# ECU_Power.net
KiCad netlist of a schematic drawn in Altium Designer
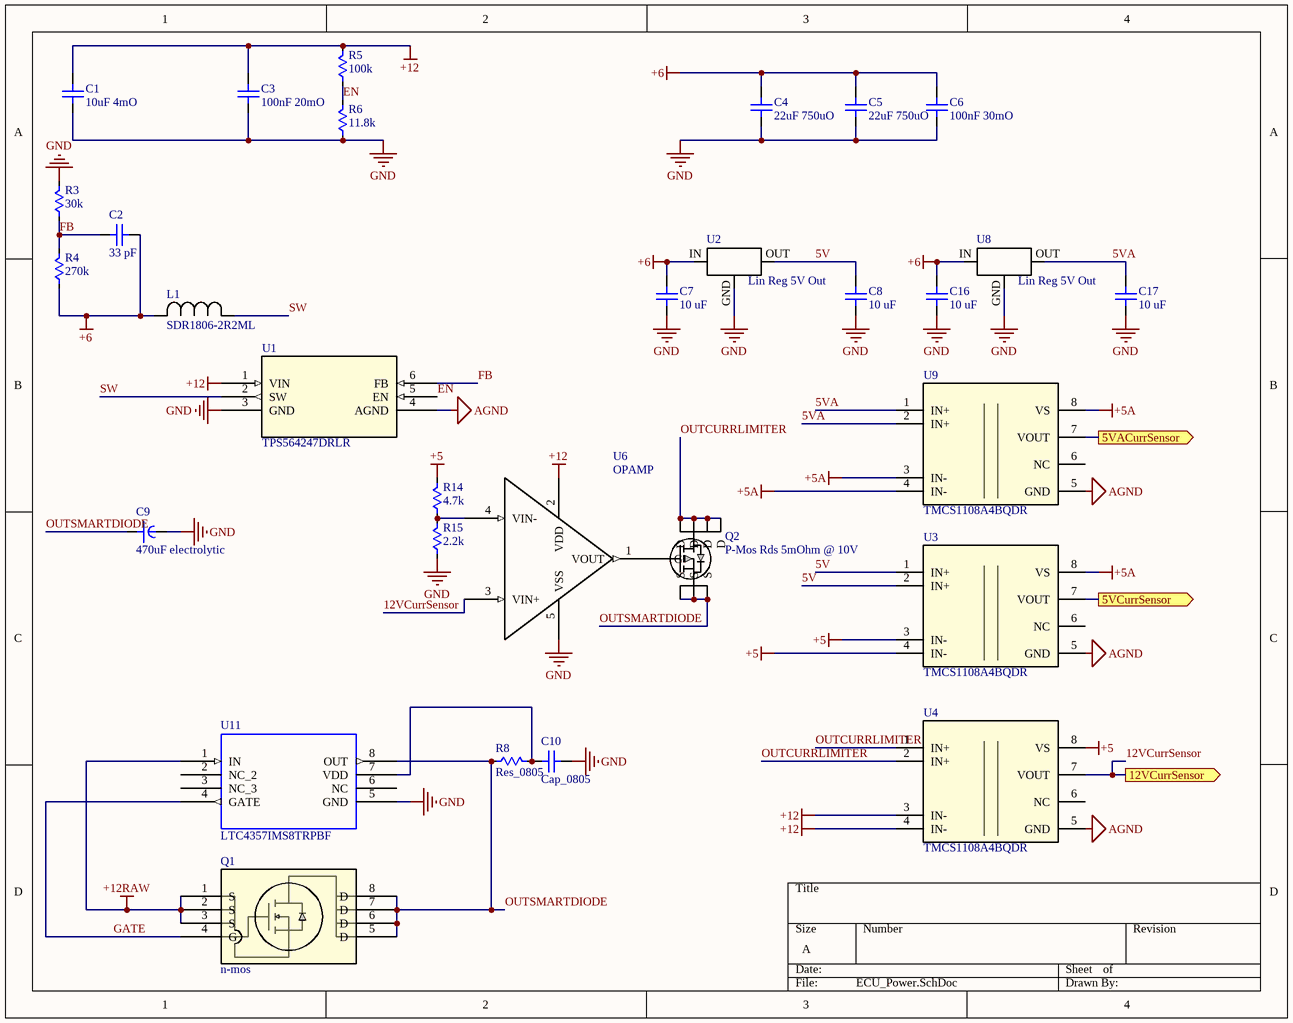
[diagram p0: ECU_Power.SchDoc]

(export (version "E")
  (design (tool "Eeschema 10.0.6"))
  (components
    (comp (ref "C1")
      (value "10uF 4mO")
      (footprint "0805")
      (description "Cap 0805")
      (libsource (lib "Caps") (part "Cap_0805"))
    )
    (comp (ref "C2")
      (value "33 pF")
      (footprint "0805")
      (description "Cap 0805 - 33 pF, 1mOhm")
      (libsource (lib "Caps") (part "Cap_0805"))
    )
    (comp (ref "C3")
      (value "100nF 20mO")
      (footprint "0805")
      (description "Cap 0805")
      (libsource (lib "Caps") (part "Cap_0805"))
    )
    (comp (ref "C4")
      (value "22uF 750uO")
      (footprint "0805")
      (description "Cap 0805")
      (libsource (lib "Caps") (part "Cap_0805"))
    )
    (comp (ref "C5")
      (value "22uF 750uO")
      (footprint "0805")
      (description "Cap 0805")
      (libsource (lib "Caps") (part "Cap_0805"))
    )
    (comp (ref "C6")
      (value "100nF 30mO")
      (footprint "0805")
      (description "Cap 0805")
      (libsource (lib "Caps") (part "Cap_0805"))
    )
    (comp (ref "C7")
      (value "10 uF")
      (footprint "0805")
      (description "Cap 0805")
      (libsource (lib "Caps") (part "Cap_0805"))
    )
    (comp (ref "C8")
      (value "10 uF")
      (footprint "0805")
      (description "Cap 0805")
      (libsource (lib "Caps") (part "Cap_0805"))
    )
    (comp (ref "C9")
      (value "470uF electrolytic")
      (footprint "CAPPRD750W80D1600H2700")
      (description "470 µF 100 V Aluminum Electrolytic Capacitors Radial, Can 282mOhm @ 120Hz 2000 Hrs @ 85°C")
      (libsource (lib "Caps") (part "CAPPRD750W80D1600H2700"))
    )
    (comp (ref "C10")
      (value "Cap_0805")
      (footprint "0805")
      (description "Cap 0805")
      (libsource (lib "Caps") (part "Cap_0805"))
    )
    (comp (ref "C16")
      (value "10 uF")
      (footprint "0805")
      (description "Cap 0805")
      (libsource (lib "Caps") (part "Cap_0805"))
    )
    (comp (ref "C17")
      (value "10 uF")
      (footprint "0805")
      (description "Cap 0805")
      (libsource (lib "Caps") (part "Cap_0805"))
    )
    (comp (ref "L1")
      (value "SDR1806-2R2ML")
      (footprint "IND_BOURNS_SDR1806")
      (description "No Description Available")
      (fields (field (name "COPYRIGHT") "Copyright (C) 2022 Ultra Librarian. All rights reserved."))
      (libsource (lib "SDR1806-2R2ML") (part "SDR1806-2R2ML"))
    )
    (comp (ref "Q1")
      (value "n-mos")
      (footprint "D0008A-IPC_A")
      (description "MOSFET MOSFETBVDSS: 25V-30V")
      (libsource (lib "DMN3007LSSQ-13") (part "DMN3007LSSQ-13"))
    )
    (comp (ref "Q2")
      (value "P-Mos Rds 5mOhm @ 10V")
      (footprint "D0008A-IPC_A")
      (description "P-Channel 30 V 16A (Ta) 2.5W (Ta) Surface Mount 8-SOP")
      (fields
        (field (name "MANUFACTURER_PART_NUMBER") "UPA2735GR-E1-AT")
        (field (name "COPYRIGHT") "Copyright (C) 2022 Ultra Librarian. All rights reserved.")
      )
      (libsource (lib "UPA2735GR-E1-AT") (part "UPA2735GR-E1-AT"))
    )
    (comp (ref "R3")
      (value "30k")
      (footprint "0805")
      (description "Res 0805 - 30kOhm")
      (libsource (lib "Resistors") (part "Res_0805"))
    )
    (comp (ref "R4")
      (value "270k")
      (footprint "0805")
      (description "Res 0805 - 270kOhm")
      (libsource (lib "Resistors") (part "Res_0805"))
    )
    (comp (ref "R5")
      (value "100k")
      (footprint "0805")
      (description "Res 0805")
      (libsource (lib "Resistors") (part "Res_0805"))
    )
    (comp (ref "R6")
      (value "11.8k")
      (footprint "0805")
      (description "Res 0805")
      (libsource (lib "Resistors") (part "Res_0805"))
    )
    (comp (ref "R8")
      (value "Res_0805")
      (footprint "0805")
      (description "Res 0805")
      (libsource (lib "Resistors") (part "Res_0805"))
    )
    (comp (ref "R14")
      (value "4.7k")
      (footprint "0805")
      (description "Res 0805")
      (libsource (lib "Resistors") (part "Res_0805"))
    )
    (comp (ref "R15")
      (value "2.2k")
      (footprint "0805")
      (description "Res 0805")
      (libsource (lib "Resistors") (part "Res_0805"))
    )
    (comp (ref "U1")
      (value "TPS564247DRLR")
      (footprint "SOT5x3-6_DRL_TEX")
      (description "No Description Available")
      (fields (field (name "COPYRIGHT") "Copyright (C) 2022 Ultra Librarian. All rights reserved."))
      (libsource (lib "TPS564247DRLR") (part "TPS564247DRLR"))
    )
    (comp (ref "U2")
      (value "Lin Reg 5V Out")
      (footprint "NCP1117IDT50T4G")
      (description "Linear Voltage Regulator IC Positive Fixed 1 Output 1A DPAK")
      (libsource (lib "NCP1117IDT50T4G") (part "NCP1117IDT50T4G"))
    )
    (comp (ref "U3")
      (value "TMCS1108A4BQDR")
      (footprint "D0008A-IPC_A")
      (description "No Description Available")
      (fields (field (name "COPYRIGHT") "Copyright (C) 2022 Ultra Librarian. All rights reserved."))
      (libsource (lib "TMCS1108A4BQDR") (part "TMCS1108A4BQDR"))
    )
    (comp (ref "U4")
      (value "TMCS1108A4BQDR")
      (footprint "D0008A-IPC_A")
      (description "No Description Available")
      (fields (field (name "COPYRIGHT") "Copyright (C) 2022 Ultra Librarian. All rights reserved."))
      (libsource (lib "TMCS1108A4BQDR") (part "TMCS1108A4BQDR"))
    )
    (comp (ref "U6")
      (value "OPAMP")
      (footprint "SOT-23-5_MC_MCH-M")
      (description "Operational Amplifiers - Op Amps Single, 10MHz Op Amp, E Temp")
      (fields
        (field (name "MANUFACTURER_PART_NUMBER") "MCP6486T-EOT")
        (field (name "COPYRIGHT") "Copyright (C) 2022 Ultra Librarian. All rights reserved.")
      )
      (libsource (lib "MCP6486T-EOT") (part "MCP6486T-EOT"))
    )
    (comp (ref "U8")
      (value "Lin Reg 5V Out")
      (footprint "NCP1117IDT50T4G")
      (description "Linear Voltage Regulator IC Positive Fixed 1 Output 1A DPAK")
      (libsource (lib "NCP1117IDT50T4G") (part "NCP1117IDT50T4G"))
    )
    (comp (ref "U9")
      (value "TMCS1108A4BQDR")
      (footprint "D0008A-IPC_A")
      (description "No Description Available")
      (fields (field (name "COPYRIGHT") "Copyright (C) 2022 Ultra Librarian. All rights reserved."))
      (libsource (lib "TMCS1108A4BQDR") (part "TMCS1108A4BQDR"))
    )
    (comp (ref "U11")
      (value "LTC4357IMS8TRPBF")
      (footprint "MSOP-8_MS:MSOP-8_MS")
      (description "OR Controller N+1 ORing Controller N-Channel N:1 8-MSOP")
      (fields (field (name "MF") "Analog Devices") (field (name "MP") "LTC4357IMS8#TRPBF"))
      (libsource (lib "LTC4357IMS8TRPBF") (part "LTC4357IMS8TRPBF"))
    )
  )
  (nets
    (net (code "1") (name "+5") (class "Default")
      (node (ref "R14") (pin "2") (pinfunction "2_2") (pintype "passive"))
      (node (ref "U3") (pin "3") (pinfunction "IN-_3") (pintype "passive"))
      (node (ref "U3") (pin "4") (pinfunction "IN-_4") (pintype "passive"))
      (node (ref "U4") (pin "8") (pinfunction "VS_8") (pintype "power_in"))
    )
    (net (code "2") (name "+5A") (class "Default")
      (node (ref "U3") (pin "8") (pinfunction "VS_8") (pintype "power_in"))
      (node (ref "U9") (pin "3") (pinfunction "IN-_3") (pintype "passive"))
      (node (ref "U9") (pin "4") (pinfunction "IN-_4") (pintype "passive"))
      (node (ref "U9") (pin "8") (pinfunction "VS_8") (pintype "power_in"))
    )
    (net (code "3") (name "+6") (class "Default")
      (node (ref "C16") (pin "2") (pinfunction "2_2") (pintype "passive"))
      (node (ref "C2") (pin "2") (pinfunction "2_2") (pintype "passive"))
      (node (ref "C4") (pin "2") (pinfunction "2_2") (pintype "passive"))
      (node (ref "C5") (pin "2") (pinfunction "2_2") (pintype "passive"))
      (node (ref "C6") (pin "2") (pinfunction "2_2") (pintype "passive"))
      (node (ref "C7") (pin "2") (pinfunction "2_2") (pintype "passive"))
      (node (ref "L1") (pin "2") (pinfunction "2_2") (pintype "passive"))
      (node (ref "R4") (pin "1") (pinfunction "1_1") (pintype "passive"))
      (node (ref "U2") (pin "IN") (pinfunction "IN_IN") (pintype "passive"))
      (node (ref "U8") (pin "IN") (pinfunction "IN_IN") (pintype "passive"))
    )
    (net (code "4") (name "+12") (class "Default")
      (node (ref "C1") (pin "2") (pinfunction "2_2") (pintype "passive"))
      (node (ref "C3") (pin "2") (pinfunction "2_2") (pintype "passive"))
      (node (ref "R5") (pin "2") (pinfunction "2_2") (pintype "passive"))
      (node (ref "U1") (pin "1") (pinfunction "VIN_1") (pintype "input"))
      (node (ref "U4") (pin "3") (pinfunction "IN-_3") (pintype "passive"))
      (node (ref "U4") (pin "4") (pinfunction "IN-_4") (pintype "passive"))
      (node (ref "U6") (pin "2") (pinfunction "VDD_2") (pintype "power_in"))
    )
    (net (code "5") (name "+12RAW") (class "Default")
      (node (ref "Q1") (pin "1") (pinfunction "S_1") (pintype "passive"))
      (node (ref "Q1") (pin "2") (pinfunction "S_2") (pintype "passive"))
      (node (ref "Q1") (pin "3") (pinfunction "S_3") (pintype "passive"))
      (node (ref "U11") (pin "1") (pinfunction "IN_1") (pintype "input"))
    )
    (net (code "6") (name "/5V") (class "Default")
      (node (ref "C8") (pin "2") (pinfunction "2_2") (pintype "passive"))
      (node (ref "U2") (pin "OUT") (pinfunction "OUT_OUT") (pintype "passive"))
      (node (ref "U3") (pin "1") (pinfunction "IN+_1") (pintype "passive"))
      (node (ref "U3") (pin "2") (pinfunction "IN+_2") (pintype "passive"))
    )
    (net (code "7") (name "/5VA") (class "Default")
      (node (ref "C17") (pin "2") (pinfunction "2_2") (pintype "passive"))
      (node (ref "U8") (pin "OUT") (pinfunction "OUT_OUT") (pintype "passive"))
      (node (ref "U9") (pin "1") (pinfunction "IN+_1") (pintype "passive"))
      (node (ref "U9") (pin "2") (pinfunction "IN+_2") (pintype "passive"))
    )
    (net (code "8") (name "/5VACurrSensor") (class "Default")
      (node (ref "U9") (pin "7") (pinfunction "VOUT_7") (pintype "passive"))
    )
    (net (code "9") (name "/5VCurrSensor") (class "Default")
      (node (ref "U3") (pin "7") (pinfunction "VOUT_7") (pintype "passive"))
    )
    (net (code "10") (name "/12VCurrSensor") (class "Default")
      (node (ref "U4") (pin "7") (pinfunction "VOUT_7") (pintype "passive"))
      (node (ref "U6") (pin "3") (pinfunction "VIN+_3") (pintype "input"))
    )
    (net (code "11") (name "/EN") (class "Default")
      (node (ref "R5") (pin "1") (pinfunction "1_1") (pintype "passive"))
      (node (ref "R6") (pin "2") (pinfunction "2_2") (pintype "passive"))
      (node (ref "U1") (pin "5") (pinfunction "EN_5") (pintype "input"))
    )
    (net (code "12") (name "/FB") (class "Default")
      (node (ref "C2") (pin "1") (pinfunction "1_1") (pintype "passive"))
      (node (ref "R3") (pin "1") (pinfunction "1_1") (pintype "passive"))
      (node (ref "R4") (pin "2") (pinfunction "2_2") (pintype "passive"))
      (node (ref "U1") (pin "6") (pinfunction "FB_6") (pintype "input"))
    )
    (net (code "13") (name "/GATE") (class "Default")
      (node (ref "Q1") (pin "4") (pinfunction "G_4") (pintype "passive"))
      (node (ref "U11") (pin "4") (pinfunction "GATE_4") (pintype "output"))
    )
    (net (code "14") (name "/OUTCURRLIMITER") (class "Default")
      (node (ref "Q2") (pin "5") (pinfunction "D_5") (pintype "passive"))
      (node (ref "Q2") (pin "6") (pinfunction "D_6") (pintype "passive"))
      (node (ref "Q2") (pin "7") (pinfunction "D_7") (pintype "passive"))
      (node (ref "Q2") (pin "8") (pinfunction "D_8") (pintype "passive"))
      (node (ref "U4") (pin "1") (pinfunction "IN+_1") (pintype "passive"))
      (node (ref "U4") (pin "2") (pinfunction "IN+_2") (pintype "passive"))
    )
    (net (code "15") (name "/OUTSMARTDIODE") (class "Default")
      (node (ref "C9") (pin "1") (pinfunction "1_1") (pintype "passive"))
      (node (ref "Q1") (pin "5") (pinfunction "D_5") (pintype "passive"))
      (node (ref "Q1") (pin "6") (pinfunction "D_6") (pintype "passive"))
      (node (ref "Q1") (pin "7") (pinfunction "D_7") (pintype "passive"))
      (node (ref "Q1") (pin "8") (pinfunction "D_8") (pintype "passive"))
      (node (ref "Q2") (pin "1") (pinfunction "S_1") (pintype "passive"))
      (node (ref "Q2") (pin "2") (pinfunction "S_2") (pintype "passive"))
      (node (ref "Q2") (pin "3") (pinfunction "S_3") (pintype "passive"))
      (node (ref "R8") (pin "1") (pinfunction "1_1") (pintype "passive"))
      (node (ref "U11") (pin "8") (pinfunction "OUT_8") (pintype "output"))
    )
    (net (code "16") (name "/SW") (class "Default")
      (node (ref "L1") (pin "1") (pinfunction "1_1") (pintype "passive"))
      (node (ref "U1") (pin "2") (pinfunction "SW_2") (pintype "output"))
    )
    (net (code "17") (name "AGND") (class "Default")
      (node (ref "U1") (pin "4") (pinfunction "AGND_4") (pintype "passive"))
      (node (ref "U3") (pin "5") (pinfunction "GND_5") (pintype "power_in"))
      (node (ref "U4") (pin "5") (pinfunction "GND_5") (pintype "power_in"))
      (node (ref "U9") (pin "5") (pinfunction "GND_5") (pintype "power_in"))
    )
    (net (code "18") (name "GND") (class "Default")
      (node (ref "C1") (pin "1") (pinfunction "1_1") (pintype "passive"))
      (node (ref "C10") (pin "2") (pinfunction "2_2") (pintype "passive"))
      (node (ref "C16") (pin "1") (pinfunction "1_1") (pintype "passive"))
      (node (ref "C17") (pin "1") (pinfunction "1_1") (pintype "passive"))
      (node (ref "C3") (pin "1") (pinfunction "1_1") (pintype "passive"))
      (node (ref "C4") (pin "1") (pinfunction "1_1") (pintype "passive"))
      (node (ref "C5") (pin "1") (pinfunction "1_1") (pintype "passive"))
      (node (ref "C6") (pin "1") (pinfunction "1_1") (pintype "passive"))
      (node (ref "C7") (pin "1") (pinfunction "1_1") (pintype "passive"))
      (node (ref "C8") (pin "1") (pinfunction "1_1") (pintype "passive"))
      (node (ref "C9") (pin "2") (pinfunction "2_2") (pintype "passive"))
      (node (ref "R15") (pin "1") (pinfunction "1_1") (pintype "passive"))
      (node (ref "R3") (pin "2") (pinfunction "2_2") (pintype "passive"))
      (node (ref "R6") (pin "1") (pinfunction "1_1") (pintype "passive"))
      (node (ref "U1") (pin "3") (pinfunction "GND_3") (pintype "passive"))
      (node (ref "U11") (pin "5") (pinfunction "GND_5") (pintype "power_in"))
      (node (ref "U2") (pin "GND") (pinfunction "GND_GND") (pintype "passive"))
      (node (ref "U6") (pin "5") (pinfunction "VSS_5") (pintype "power_in"))
      (node (ref "U8") (pin "GND") (pinfunction "GND_GND") (pintype "passive"))
    )
    (net (code "19") (name "Net-(Q2-G)") (class "Default")
      (node (ref "Q2") (pin "4") (pinfunction "G_4") (pintype "passive"))
      (node (ref "U6") (pin "1") (pinfunction "VOUT_1") (pintype "output"))
    )
    (net (code "20") (name "Net-(U6-VIN-)") (class "Default")
      (node (ref "R14") (pin "1") (pinfunction "1_1") (pintype "passive"))
      (node (ref "R15") (pin "2") (pinfunction "2_2") (pintype "passive"))
      (node (ref "U6") (pin "4") (pinfunction "VIN-_4") (pintype "input"))
    )
    (net (code "21") (name "Net-(U11-VDD)") (class "Default")
      (node (ref "C10") (pin "1") (pinfunction "1_1") (pintype "passive"))
      (node (ref "R8") (pin "2") (pinfunction "2_2") (pintype "passive"))
      (node (ref "U11") (pin "7") (pinfunction "VDD_7") (pintype "power_in"))
    )
    (net (code "22") (name "unconnected-(U3-NC-Pad6)") (class "Default")
      (node (ref "U3") (pin "6") (pinfunction "NC_6") (pintype "passive"))
    )
    (net (code "23") (name "unconnected-(U4-NC-Pad6)") (class "Default")
      (node (ref "U4") (pin "6") (pinfunction "NC_6") (pintype "passive"))
    )
    (net (code "24") (name "unconnected-(U9-NC-Pad6)") (class "Default")
      (node (ref "U9") (pin "6") (pinfunction "NC_6") (pintype "passive"))
    )
    (net (code "25") (name "unconnected-(U11-NC-Pad6)") (class "Default")
      (node (ref "U11") (pin "6") (pinfunction "NC_6") (pintype "passive"))
    )
    (net (code "26") (name "unconnected-(U11-NC_2-Pad2)") (class "Default")
      (node (ref "U11") (pin "2") (pinfunction "NC_2_2") (pintype "passive"))
    )
    (net (code "27") (name "unconnected-(U11-NC_3-Pad3)") (class "Default")
      (node (ref "U11") (pin "3") (pinfunction "NC_3_3") (pintype "passive"))
    )
  )
)
